# 08_SAMA7G54-DDR3.net
KiCad netlist of a schematic drawn in Altium Designer
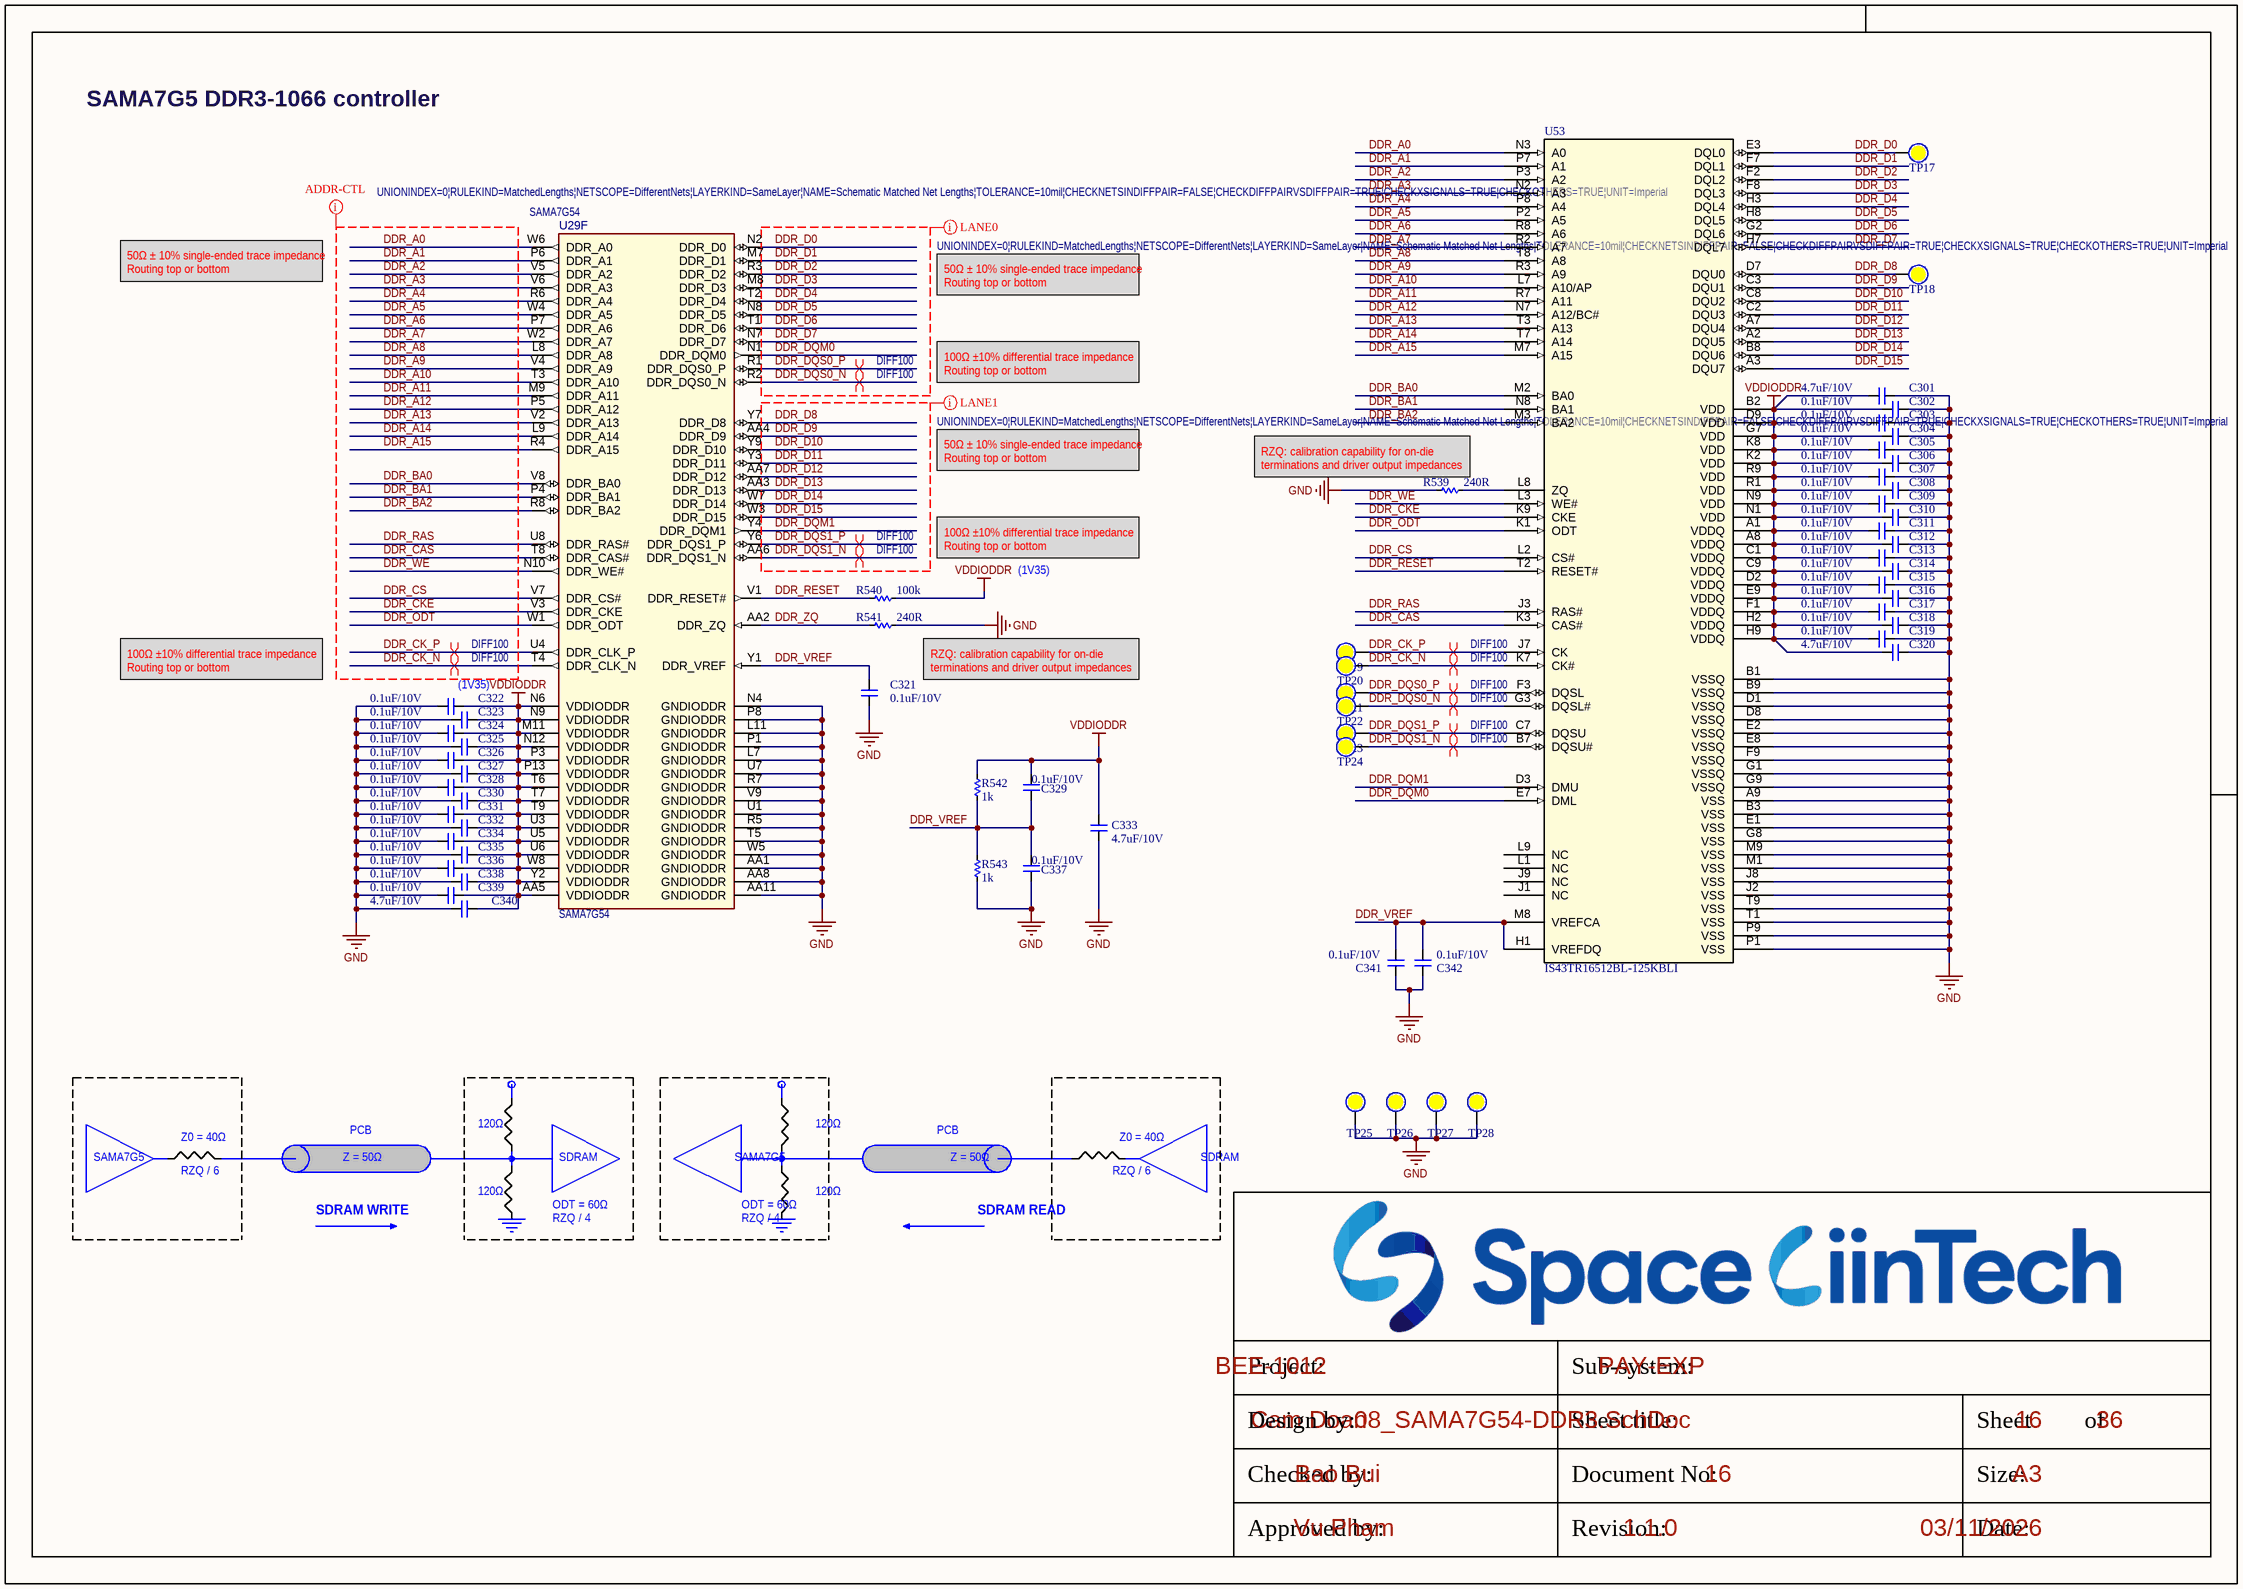
[diagram p0: 08_SAMA7G54-DDR3.SchDoc]

(export (version "E")
  (design (tool "Eeschema 10.0.6"))
  (components
    (comp (ref "C301")
      (value "4.7uF/10V")
      (footprint "CAP_C_1005X50_L")
      (description "CAP")
      (libsource (lib "LABLIB") (part "_CAP_C_2"))
    )
    (comp (ref "C302")
      (value "0.1uF/10V")
      (footprint "CAP_C_0603x30")
      (description "CAP")
      (libsource (lib "LABLIB") (part "_CAP_C_2"))
    )
    (comp (ref "C303")
      (value "0.1uF/10V")
      (footprint "CAP_C_0603x30")
      (description "CAP")
      (libsource (lib "LABLIB") (part "_CAP_C_2"))
    )
    (comp (ref "C304")
      (value "0.1uF/10V")
      (footprint "CAP_C_0603x30")
      (description "CAP")
      (libsource (lib "LABLIB") (part "_CAP_C_2"))
    )
    (comp (ref "C305")
      (value "0.1uF/10V")
      (footprint "CAP_C_0603x30")
      (description "CAP")
      (libsource (lib "LABLIB") (part "_CAP_C_2"))
    )
    (comp (ref "C306")
      (value "0.1uF/10V")
      (footprint "CAP_C_0603x30")
      (description "CAP")
      (libsource (lib "LABLIB") (part "_CAP_C_2"))
    )
    (comp (ref "C307")
      (value "0.1uF/10V")
      (footprint "CAP_C_0603x30")
      (description "CAP")
      (libsource (lib "LABLIB") (part "_CAP_C_2"))
    )
    (comp (ref "C308")
      (value "0.1uF/10V")
      (footprint "CAP_C_0603x30")
      (description "CAP")
      (libsource (lib "LABLIB") (part "_CAP_C_2"))
    )
    (comp (ref "C309")
      (value "0.1uF/10V")
      (footprint "CAP_C_0603x30")
      (description "CAP")
      (libsource (lib "LABLIB") (part "_CAP_C_2"))
    )
    (comp (ref "C310")
      (value "0.1uF/10V")
      (footprint "CAP_C_0603x30")
      (description "CAP")
      (libsource (lib "LABLIB") (part "_CAP_C_2"))
    )
    (comp (ref "C311")
      (value "0.1uF/10V")
      (footprint "CAP_C_0603x30")
      (description "CAP")
      (libsource (lib "LABLIB") (part "_CAP_C_2"))
    )
    (comp (ref "C312")
      (value "0.1uF/10V")
      (footprint "CAP_C_0603x30")
      (description "CAP")
      (libsource (lib "LABLIB") (part "_CAP_C_2"))
    )
    (comp (ref "C313")
      (value "0.1uF/10V")
      (footprint "CAP_C_0603x30")
      (description "CAP")
      (libsource (lib "LABLIB") (part "_CAP_C_2"))
    )
    (comp (ref "C314")
      (value "0.1uF/10V")
      (footprint "CAP_C_0603x30")
      (description "CAP")
      (libsource (lib "LABLIB") (part "_CAP_C_2"))
    )
    (comp (ref "C315")
      (value "0.1uF/10V")
      (footprint "CAP_C_0603x30")
      (description "CAP")
      (libsource (lib "LABLIB") (part "_CAP_C_2"))
    )
    (comp (ref "C316")
      (value "0.1uF/10V")
      (footprint "CAP_C_0603x30")
      (description "CAP")
      (libsource (lib "LABLIB") (part "_CAP_C_2"))
    )
    (comp (ref "C317")
      (value "0.1uF/10V")
      (footprint "CAP_C_0603x30")
      (description "CAP")
      (libsource (lib "LABLIB") (part "_CAP_C_2"))
    )
    (comp (ref "C318")
      (value "0.1uF/10V")
      (footprint "CAP_C_0603x30")
      (description "CAP")
      (libsource (lib "LABLIB") (part "_CAP_C_2"))
    )
    (comp (ref "C319")
      (value "0.1uF/10V")
      (footprint "CAP_C_0603x30")
      (description "CAP")
      (libsource (lib "LABLIB") (part "_CAP_C_2"))
    )
    (comp (ref "C320")
      (value "4.7uF/10V")
      (footprint "CAP_C_1005X50_L")
      (description "CAP")
      (libsource (lib "LABLIB") (part "_CAP_C_2"))
    )
    (comp (ref "C321")
      (value "0.1uF/10V")
      (footprint "CAP_C_0603x30")
      (description "CAP")
      (libsource (lib "LABLIB") (part "_CAP_C_2"))
    )
    (comp (ref "C322")
      (value "0.1uF/10V")
      (footprint "CAP_C_0603x30")
      (description "CAP")
      (libsource (lib "LABLIB") (part "_CAP_C_2"))
    )
    (comp (ref "C323")
      (value "0.1uF/10V")
      (footprint "CAP_C_0603x30")
      (description "CAP")
      (libsource (lib "LABLIB") (part "_CAP_C_2"))
    )
    (comp (ref "C324")
      (value "0.1uF/10V")
      (footprint "CAP_C_0603x30")
      (description "CAP")
      (libsource (lib "LABLIB") (part "_CAP_C_2"))
    )
    (comp (ref "C325")
      (value "0.1uF/10V")
      (footprint "CAP_C_0603x30")
      (description "CAP")
      (libsource (lib "LABLIB") (part "_CAP_C_2"))
    )
    (comp (ref "C326")
      (value "0.1uF/10V")
      (footprint "CAP_C_0603x30")
      (description "CAP")
      (libsource (lib "LABLIB") (part "_CAP_C_2"))
    )
    (comp (ref "C327")
      (value "0.1uF/10V")
      (footprint "CAP_C_0603x30")
      (description "CAP")
      (libsource (lib "LABLIB") (part "_CAP_C_2"))
    )
    (comp (ref "C328")
      (value "0.1uF/10V")
      (footprint "CAP_C_0603x30")
      (description "CAP")
      (libsource (lib "LABLIB") (part "_CAP_C_2"))
    )
    (comp (ref "C329")
      (value "0.1uF/10V")
      (footprint "CAP_C_0603x30")
      (description "CAP")
      (libsource (lib "LABLIB") (part "_CAP_C_2"))
    )
    (comp (ref "C330")
      (value "0.1uF/10V")
      (footprint "CAP_C_0603x30")
      (description "CAP")
      (libsource (lib "LABLIB") (part "_CAP_C_2"))
    )
    (comp (ref "C331")
      (value "0.1uF/10V")
      (footprint "CAP_C_0603x30")
      (description "CAP")
      (libsource (lib "LABLIB") (part "_CAP_C_2"))
    )
    (comp (ref "C332")
      (value "0.1uF/10V")
      (footprint "CAP_C_0603x30")
      (description "CAP")
      (libsource (lib "LABLIB") (part "_CAP_C_2"))
    )
    (comp (ref "C333")
      (value "4.7uF/10V")
      (footprint "CAP_C_1005X50_L")
      (description "CAP")
      (libsource (lib "LABLIB") (part "_CAP_C_2"))
    )
    (comp (ref "C334")
      (value "0.1uF/10V")
      (footprint "CAP_C_0603x30")
      (description "CAP")
      (libsource (lib "LABLIB") (part "_CAP_C_2"))
    )
    (comp (ref "C335")
      (value "0.1uF/10V")
      (footprint "CAP_C_0603x30")
      (description "CAP")
      (libsource (lib "LABLIB") (part "_CAP_C_2"))
    )
    (comp (ref "C336")
      (value "0.1uF/10V")
      (footprint "CAP_C_0603x30")
      (description "CAP")
      (libsource (lib "LABLIB") (part "_CAP_C_2"))
    )
    (comp (ref "C337")
      (value "0.1uF/10V")
      (footprint "CAP_C_0603x30")
      (description "CAP")
      (libsource (lib "LABLIB") (part "_CAP_C_2"))
    )
    (comp (ref "C338")
      (value "0.1uF/10V")
      (footprint "CAP_C_0603x30")
      (description "CAP")
      (libsource (lib "LABLIB") (part "_CAP_C_2"))
    )
    (comp (ref "C339")
      (value "0.1uF/10V")
      (footprint "CAP_C_0603x30")
      (description "CAP")
      (libsource (lib "LABLIB") (part "_CAP_C_2"))
    )
    (comp (ref "C340")
      (value "4.7uF/10V")
      (footprint "CAP_C_1005X50_L")
      (description "CAP")
      (libsource (lib "LABLIB") (part "_CAP_C_2"))
    )
    (comp (ref "C341")
      (value "0.1uF/10V")
      (footprint "CAP_C_0603x30")
      (description "CAP")
      (libsource (lib "LABLIB") (part "_CAP_C_2"))
    )
    (comp (ref "C342")
      (value "0.1uF/10V")
      (footprint "CAP_C_0603x30")
      (description "CAP")
      (libsource (lib "LABLIB") (part "_CAP_C_2"))
    )
    (comp (ref "R539")
      (value "240R")
      (footprint "RES_C_0603X30")
      (description "RES")
      (libsource (lib "LABLIB") (part "_RES_B_2"))
    )
    (comp (ref "R540")
      (value "100k")
      (footprint "RES_C_0603X30")
      (description "RES")
      (libsource (lib "LABLIB") (part "_RES_B_2"))
    )
    (comp (ref "R541")
      (value "240R")
      (footprint "RES_C_0603X30")
      (description "RES")
      (libsource (lib "LABLIB") (part "_RES_B_2"))
    )
    (comp (ref "R542")
      (value "1k")
      (footprint "RES_C_0603X30")
      (description "RES")
      (libsource (lib "LABLIB") (part "_RES_B_2"))
    )
    (comp (ref "R543")
      (value "1k")
      (footprint "RES_C_0603X30")
      (description "RES")
      (libsource (lib "LABLIB") (part "_RES_B_2"))
    )
    (comp (ref "TP17")
      (value "~")
      (footprint "Testpoint_50")
      (description "Test Point")
      (libsource (lib "") (part "Test Point_2"))
    )
    (comp (ref "TP18")
      (value "~")
      (footprint "Testpoint_50")
      (description "Test Point")
      (libsource (lib "") (part "Test Point_2"))
    )
    (comp (ref "TP19")
      (value "~")
      (footprint "Testpoint_50")
      (description "Test Point")
      (libsource (lib "LABLIB") (part "Test Point"))
    )
    (comp (ref "TP20")
      (value "~")
      (footprint "Testpoint_50")
      (description "Test Point")
      (libsource (lib "LABLIB") (part "Test Point"))
    )
    (comp (ref "TP21")
      (value "~")
      (footprint "Testpoint_50")
      (description "Test Point")
      (libsource (lib "LABLIB") (part "Test Point"))
    )
    (comp (ref "TP22")
      (value "~")
      (footprint "Testpoint_50")
      (description "Test Point")
      (libsource (lib "LABLIB") (part "Test Point"))
    )
    (comp (ref "TP23")
      (value "~")
      (footprint "Testpoint_50")
      (description "Test Point")
      (libsource (lib "LABLIB") (part "Test Point"))
    )
    (comp (ref "TP24")
      (value "~")
      (footprint "Testpoint_50")
      (description "Test Point")
      (libsource (lib "LABLIB") (part "Test Point"))
    )
    (comp (ref "TP25")
      (value "~")
      (footprint "Testpoint_50")
      (description "Test Point")
      (libsource (lib "") (part "Test Point_1"))
    )
    (comp (ref "TP26")
      (value "~")
      (footprint "Testpoint_50")
      (description "Test Point")
      (libsource (lib "") (part "Test Point_1"))
    )
    (comp (ref "TP27")
      (value "~")
      (footprint "Testpoint_50")
      (description "Test Point")
      (libsource (lib "") (part "Test Point_1"))
    )
    (comp (ref "TP28")
      (value "~")
      (footprint "Testpoint_50")
      (description "Test Point")
      (libsource (lib "") (part "Test Point_1"))
    )
    (comp (ref "U29")
      (value "SAMA7G54")
      (footprint "TFBGA-343_14x14 - 2.5mm")
      (description "SAMA7G54 MPU 1000MHz Cortex-A7 TFBGA-343")
      (fields (field (name "ALTIUM_VALUE") "SAMA7G54") (field (name "OWNER") "Ciprian Abramov"))
      (libsource (lib "LABLIB") (part "SAMA7G54"))
    )
    (comp (ref "U53")
      (value "IS43TR16512BL-125KBLI")
      (footprint "TWBGA96_ISI")
      (description "DDR3L")
      (fields (field (name "COPYRIGHT") "Copyright (C) 2025 Ultra Librarian. All rights reserved."))
      (libsource (lib "LABLIB") (part "IC_RAM_IS43TR16512BL-125KBLI"))
    )
  )
  (nets
    (net (code "1") (name "/DDR_A0") (class "Default")
      (node (ref "U29") (pin "W6") (pinfunction "DDR_A0_W6") (pintype "output"))
      (node (ref "U53") (pin "N3") (pinfunction "A0_N3") (pintype "input"))
    )
    (net (code "2") (name "/DDR_A1") (class "Default")
      (node (ref "U29") (pin "P6") (pinfunction "DDR_A1_P6") (pintype "output"))
      (node (ref "U53") (pin "P7") (pinfunction "A1_P7") (pintype "input"))
    )
    (net (code "3") (name "/DDR_A2") (class "Default")
      (node (ref "U29") (pin "V5") (pinfunction "DDR_A2_V5") (pintype "output"))
      (node (ref "U53") (pin "P3") (pinfunction "A2_P3") (pintype "input"))
    )
    (net (code "4") (name "/DDR_A3") (class "Default")
      (node (ref "U29") (pin "V6") (pinfunction "DDR_A3_V6") (pintype "output"))
      (node (ref "U53") (pin "N2") (pinfunction "A3_N2") (pintype "input"))
    )
    (net (code "5") (name "/DDR_A4") (class "Default")
      (node (ref "U29") (pin "R6") (pinfunction "DDR_A4_R6") (pintype "output"))
      (node (ref "U53") (pin "P8") (pinfunction "A4_P8") (pintype "input"))
    )
    (net (code "6") (name "/DDR_A5") (class "Default")
      (node (ref "U29") (pin "W4") (pinfunction "DDR_A5_W4") (pintype "output"))
      (node (ref "U53") (pin "P2") (pinfunction "A5_P2") (pintype "input"))
    )
    (net (code "7") (name "/DDR_A6") (class "Default")
      (node (ref "U29") (pin "P7") (pinfunction "DDR_A6_P7") (pintype "output"))
      (node (ref "U53") (pin "R8") (pinfunction "A6_R8") (pintype "input"))
    )
    (net (code "8") (name "/DDR_A7") (class "Default")
      (node (ref "U29") (pin "W2") (pinfunction "DDR_A7_W2") (pintype "output"))
      (node (ref "U53") (pin "R2") (pinfunction "A7_R2") (pintype "input"))
    )
    (net (code "9") (name "/DDR_A8") (class "Default")
      (node (ref "U29") (pin "L8") (pinfunction "DDR_A8_L8") (pintype "output"))
      (node (ref "U53") (pin "T8") (pinfunction "A8_T8") (pintype "input"))
    )
    (net (code "10") (name "/DDR_A9") (class "Default")
      (node (ref "U29") (pin "V4") (pinfunction "DDR_A9_V4") (pintype "output"))
      (node (ref "U53") (pin "R3") (pinfunction "A9_R3") (pintype "input"))
    )
    (net (code "11") (name "/DDR_A10") (class "Default")
      (node (ref "U29") (pin "T3") (pinfunction "DDR_A10_T3") (pintype "output"))
      (node (ref "U53") (pin "L7") (pinfunction "A10/AP_L7") (pintype "input"))
    )
    (net (code "12") (name "/DDR_A11") (class "Default")
      (node (ref "U29") (pin "M9") (pinfunction "DDR_A11_M9") (pintype "output"))
      (node (ref "U53") (pin "R7") (pinfunction "A11_R7") (pintype "input"))
    )
    (net (code "13") (name "/DDR_A12") (class "Default")
      (node (ref "U29") (pin "P5") (pinfunction "DDR_A12_P5") (pintype "output"))
      (node (ref "U53") (pin "N7") (pinfunction "A12/BC#_N7") (pintype "input"))
    )
    (net (code "14") (name "/DDR_A13") (class "Default")
      (node (ref "U29") (pin "V2") (pinfunction "DDR_A13_V2") (pintype "output"))
      (node (ref "U53") (pin "T3") (pinfunction "A13_T3") (pintype "input"))
    )
    (net (code "15") (name "/DDR_A14") (class "Default")
      (node (ref "U29") (pin "L9") (pinfunction "DDR_A14_L9") (pintype "output"))
      (node (ref "U53") (pin "T7") (pinfunction "A14_T7") (pintype "input"))
    )
    (net (code "16") (name "/DDR_A15") (class "Default")
      (node (ref "U29") (pin "R4") (pinfunction "DDR_A15_R4") (pintype "output"))
      (node (ref "U53") (pin "M7") (pinfunction "A15_M7") (pintype "input"))
    )
    (net (code "17") (name "/DDR_BA0") (class "Default")
      (node (ref "U29") (pin "V8") (pinfunction "DDR_BA0_V8") (pintype "bidirectional"))
      (node (ref "U53") (pin "M2") (pinfunction "BA0_M2") (pintype "input"))
    )
    (net (code "18") (name "/DDR_BA1") (class "Default")
      (node (ref "U29") (pin "P4") (pinfunction "DDR_BA1_P4") (pintype "bidirectional"))
      (node (ref "U53") (pin "N8") (pinfunction "BA1_N8") (pintype "input"))
    )
    (net (code "19") (name "/DDR_BA2") (class "Default")
      (node (ref "U29") (pin "R8") (pinfunction "DDR_BA2_R8") (pintype "bidirectional"))
      (node (ref "U53") (pin "M3") (pinfunction "BA2_M3") (pintype "input"))
    )
    (net (code "20") (name "/DDR_CAS") (class "Default")
      (node (ref "U29") (pin "T8") (pinfunction "DDR_CAS#_T8") (pintype "bidirectional"))
      (node (ref "U53") (pin "K3") (pinfunction "CAS#_K3") (pintype "input"))
    )
    (net (code "21") (name "/DDR_CKE") (class "Default")
      (node (ref "U29") (pin "V3") (pinfunction "DDR_CKE_V3") (pintype "output"))
      (node (ref "U53") (pin "K9") (pinfunction "CKE_K9") (pintype "input"))
    )
    (net (code "22") (name "/DDR_CK_N") (class "Default")
      (node (ref "TP20") (pin "1") (pinfunction "1_1") (pintype "passive"))
      (node (ref "U29") (pin "T4") (pinfunction "DDR_CLK_N_T4") (pintype "output"))
      (node (ref "U53") (pin "K7") (pinfunction "CK#_K7") (pintype "input"))
    )
    (net (code "23") (name "/DDR_CK_P") (class "Default")
      (node (ref "TP19") (pin "1") (pinfunction "1_1") (pintype "passive"))
      (node (ref "U29") (pin "U4") (pinfunction "DDR_CLK_P_U4") (pintype "output"))
      (node (ref "U53") (pin "J7") (pinfunction "CK_J7") (pintype "input"))
    )
    (net (code "24") (name "/DDR_CS") (class "Default")
      (node (ref "U29") (pin "V7") (pinfunction "DDR_CS#_V7") (pintype "output"))
      (node (ref "U53") (pin "L2") (pinfunction "CS#_L2") (pintype "input"))
    )
    (net (code "25") (name "/DDR_D0") (class "Default")
      (node (ref "TP17") (pin "1") (pinfunction "1_1") (pintype "passive"))
      (node (ref "U29") (pin "N2") (pinfunction "DDR_D0_N2") (pintype "bidirectional"))
      (node (ref "U53") (pin "E3") (pinfunction "DQL0_E3") (pintype "bidirectional"))
    )
    (net (code "26") (name "/DDR_D1") (class "Default")
      (node (ref "U29") (pin "M7") (pinfunction "DDR_D1_M7") (pintype "bidirectional"))
      (node (ref "U53") (pin "F7") (pinfunction "DQL1_F7") (pintype "bidirectional"))
    )
    (net (code "27") (name "/DDR_D2") (class "Default")
      (node (ref "U29") (pin "R3") (pinfunction "DDR_D2_R3") (pintype "bidirectional"))
      (node (ref "U53") (pin "F2") (pinfunction "DQL2_F2") (pintype "bidirectional"))
    )
    (net (code "28") (name "/DDR_D3") (class "Default")
      (node (ref "U29") (pin "M8") (pinfunction "DDR_D3_M8") (pintype "bidirectional"))
      (node (ref "U53") (pin "F8") (pinfunction "DQL3_F8") (pintype "bidirectional"))
    )
    (net (code "29") (name "/DDR_D4") (class "Default")
      (node (ref "U29") (pin "T2") (pinfunction "DDR_D4_T2") (pintype "bidirectional"))
      (node (ref "U53") (pin "H3") (pinfunction "DQL4_H3") (pintype "bidirectional"))
    )
    (net (code "30") (name "/DDR_D5") (class "Default")
      (node (ref "U29") (pin "N8") (pinfunction "DDR_D5_N8") (pintype "bidirectional"))
      (node (ref "U53") (pin "H8") (pinfunction "DQL5_H8") (pintype "bidirectional"))
    )
    (net (code "31") (name "/DDR_D6") (class "Default")
      (node (ref "U29") (pin "T1") (pinfunction "DDR_D6_T1") (pintype "bidirectional"))
      (node (ref "U53") (pin "G2") (pinfunction "DQL6_G2") (pintype "bidirectional"))
    )
    (net (code "32") (name "/DDR_D7") (class "Default")
      (node (ref "U29") (pin "N7") (pinfunction "DDR_D7_N7") (pintype "bidirectional"))
      (node (ref "U53") (pin "H7") (pinfunction "DQL7_H7") (pintype "bidirectional"))
    )
    (net (code "33") (name "/DDR_D8") (class "Default")
      (node (ref "TP18") (pin "1") (pinfunction "1_1") (pintype "passive"))
      (node (ref "U29") (pin "Y7") (pinfunction "DDR_D8_Y7") (pintype "bidirectional"))
      (node (ref "U53") (pin "D7") (pinfunction "DQU0_D7") (pintype "bidirectional"))
    )
    (net (code "34") (name "/DDR_D9") (class "Default")
      (node (ref "U29") (pin "AA4") (pinfunction "DDR_D9_AA4") (pintype "bidirectional"))
      (node (ref "U53") (pin "C3") (pinfunction "DQU1_C3") (pintype "bidirectional"))
    )
    (net (code "35") (name "/DDR_D10") (class "Default")
      (node (ref "U29") (pin "Y9") (pinfunction "DDR_D10_Y9") (pintype "bidirectional"))
      (node (ref "U53") (pin "C8") (pinfunction "DQU2_C8") (pintype "bidirectional"))
    )
    (net (code "36") (name "/DDR_D11") (class "Default")
      (node (ref "U29") (pin "Y3") (pinfunction "DDR_D11_Y3") (pintype "bidirectional"))
      (node (ref "U53") (pin "C2") (pinfunction "DQU3_C2") (pintype "bidirectional"))
    )
    (net (code "37") (name "/DDR_D12") (class "Default")
      (node (ref "U29") (pin "AA7") (pinfunction "DDR_D12_AA7") (pintype "bidirectional"))
      (node (ref "U53") (pin "A7") (pinfunction "DQU4_A7") (pintype "bidirectional"))
    )
    (net (code "38") (name "/DDR_D13") (class "Default")
      (node (ref "U29") (pin "AA3") (pinfunction "DDR_D13_AA3") (pintype "bidirectional"))
      (node (ref "U53") (pin "A2") (pinfunction "DQU5_A2") (pintype "bidirectional"))
    )
    (net (code "39") (name "/DDR_D14") (class "Default")
      (node (ref "U29") (pin "W7") (pinfunction "DDR_D14_W7") (pintype "bidirectional"))
      (node (ref "U53") (pin "B8") (pinfunction "DQU6_B8") (pintype "bidirectional"))
    )
    (net (code "40") (name "/DDR_D15") (class "Default")
      (node (ref "U29") (pin "W3") (pinfunction "DDR_D15_W3") (pintype "bidirectional"))
      (node (ref "U53") (pin "A3") (pinfunction "DQU7_A3") (pintype "bidirectional"))
    )
    (net (code "41") (name "/DDR_DQM0") (class "Default")
      (node (ref "U29") (pin "N1") (pinfunction "DDR_DQM0_N1") (pintype "output"))
      (node (ref "U53") (pin "E7") (pinfunction "DML_E7") (pintype "input"))
    )
    (net (code "42") (name "/DDR_DQM1") (class "Default")
      (node (ref "U29") (pin "Y4") (pinfunction "DDR_DQM1_Y4") (pintype "output"))
      (node (ref "U53") (pin "D3") (pinfunction "DMU_D3") (pintype "input"))
    )
    (net (code "43") (name "/DDR_DQS0_N") (class "Default")
      (node (ref "TP22") (pin "1") (pinfunction "1_1") (pintype "passive"))
      (node (ref "U29") (pin "R2") (pinfunction "DDR_DQS0_N_R2") (pintype "bidirectional"))
      (node (ref "U53") (pin "G3") (pinfunction "DQSL#_G3") (pintype "bidirectional"))
    )
    (net (code "44") (name "/DDR_DQS0_P") (class "Default")
      (node (ref "TP21") (pin "1") (pinfunction "1_1") (pintype "passive"))
      (node (ref "U29") (pin "R1") (pinfunction "DDR_DQS0_P_R1") (pintype "bidirectional"))
      (node (ref "U53") (pin "F3") (pinfunction "DQSL_F3") (pintype "bidirectional"))
    )
    (net (code "45") (name "/DDR_DQS1_N") (class "Default")
      (node (ref "TP24") (pin "1") (pinfunction "1_1") (pintype "passive"))
      (node (ref "U29") (pin "AA6") (pinfunction "DDR_DQS1_N_AA6") (pintype "bidirectional"))
      (node (ref "U53") (pin "B7") (pinfunction "DQSU#_B7") (pintype "bidirectional"))
    )
    (net (code "46") (name "/DDR_DQS1_P") (class "Default")
      (node (ref "TP23") (pin "1") (pinfunction "1_1") (pintype "passive"))
      (node (ref "U29") (pin "Y6") (pinfunction "DDR_DQS1_P_Y6") (pintype "bidirectional"))
      (node (ref "U53") (pin "C7") (pinfunction "DQSU_C7") (pintype "bidirectional"))
    )
    (net (code "47") (name "/DDR_ODT") (class "Default")
      (node (ref "U29") (pin "W1") (pinfunction "DDR_ODT_W1") (pintype "output"))
      (node (ref "U53") (pin "K1") (pinfunction "ODT_K1") (pintype "input"))
    )
    (net (code "48") (name "/DDR_RAS") (class "Default")
      (node (ref "U29") (pin "U8") (pinfunction "DDR_RAS#_U8") (pintype "bidirectional"))
      (node (ref "U53") (pin "J3") (pinfunction "RAS#_J3") (pintype "input"))
    )
    (net (code "49") (name "/DDR_RESET") (class "Default")
      (node (ref "R540") (pin "2") (pinfunction "2_2") (pintype "passive"))
      (node (ref "U29") (pin "V1") (pinfunction "DDR_RESET#_V1") (pintype "output"))
      (node (ref "U53") (pin "T2") (pinfunction "RESET#_T2") (pintype "input"))
    )
    (net (code "50") (name "/DDR_VREF") (class "Default")
      (node (ref "C321") (pin "1") (pinfunction "1_1") (pintype "passive"))
      (node (ref "C329") (pin "2") (pinfunction "2_2") (pintype "passive"))
      (node (ref "C337") (pin "1") (pinfunction "1_1") (pintype "passive"))
      (node (ref "C341") (pin "1") (pinfunction "1_1") (pintype "passive"))
      (node (ref "C342") (pin "1") (pinfunction "1_1") (pintype "passive"))
      (node (ref "R542") (pin "2") (pinfunction "2_2") (pintype "passive"))
      (node (ref "R543") (pin "1") (pinfunction "1_1") (pintype "passive"))
      (node (ref "U29") (pin "Y1") (pinfunction "DDR_VREF_Y1") (pintype "input"))
      (node (ref "U53") (pin "H1") (pinfunction "VREFDQ_H1") (pintype "power_in"))
      (node (ref "U53") (pin "M8") (pinfunction "VREFCA_M8") (pintype "power_in"))
    )
    (net (code "51") (name "/DDR_WE") (class "Default")
      (node (ref "U29") (pin "N10") (pinfunction "DDR_WE#_N10") (pintype "output"))
      (node (ref "U53") (pin "L3") (pinfunction "WE#_L3") (pintype "input"))
    )
    (net (code "52") (name "/DDR_ZQ") (class "Default")
      (node (ref "R541") (pin "2") (pinfunction "2_2") (pintype "passive"))
      (node (ref "U29") (pin "AA2") (pinfunction "DDR_ZQ_AA2") (pintype "input"))
    )
    (net (code "53") (name "GND") (class "Default")
      (node (ref "C301") (pin "1") (pinfunction "1_1") (pintype "passive"))
      (node (ref "C302") (pin "1") (pinfunction "1_1") (pintype "passive"))
      (node (ref "C303") (pin "1") (pinfunction "1_1") (pintype "passive"))
      (node (ref "C304") (pin "1") (pinfunction "1_1") (pintype "passive"))
      (node (ref "C305") (pin "1") (pinfunction "1_1") (pintype "passive"))
      (node (ref "C306") (pin "1") (pinfunction "1_1") (pintype "passive"))
      (node (ref "C307") (pin "1") (pinfunction "1_1") (pintype "passive"))
      (node (ref "C308") (pin "1") (pinfunction "1_1") (pintype "passive"))
      (node (ref "C309") (pin "1") (pinfunction "1_1") (pintype "passive"))
      (node (ref "C310") (pin "1") (pinfunction "1_1") (pintype "passive"))
      (node (ref "C311") (pin "1") (pinfunction "1_1") (pintype "passive"))
      (node (ref "C312") (pin "1") (pinfunction "1_1") (pintype "passive"))
      (node (ref "C313") (pin "1") (pinfunction "1_1") (pintype "passive"))
      (node (ref "C314") (pin "1") (pinfunction "1_1") (pintype "passive"))
      (node (ref "C315") (pin "1") (pinfunction "1_1") (pintype "passive"))
      (node (ref "C316") (pin "1") (pinfunction "1_1") (pintype "passive"))
      (node (ref "C317") (pin "1") (pinfunction "1_1") (pintype "passive"))
      (node (ref "C318") (pin "1") (pinfunction "1_1") (pintype "passive"))
      (node (ref "C319") (pin "1") (pinfunction "1_1") (pintype "passive"))
      (node (ref "C320") (pin "1") (pinfunction "1_1") (pintype "passive"))
      (node (ref "C321") (pin "2") (pinfunction "2_2") (pintype "passive"))
      (node (ref "C322") (pin "2") (pinfunction "2_2") (pintype "passive"))
      (node (ref "C323") (pin "2") (pinfunction "2_2") (pintype "passive"))
      (node (ref "C324") (pin "2") (pinfunction "2_2") (pintype "passive"))
      (node (ref "C325") (pin "2") (pinfunction "2_2") (pintype "passive"))
      (node (ref "C326") (pin "2") (pinfunction "2_2") (pintype "passive"))
      (node (ref "C327") (pin "2") (pinfunction "2_2") (pintype "passive"))
      (node (ref "C328") (pin "2") (pinfunction "2_2") (pintype "passive"))
      (node (ref "C330") (pin "2") (pinfunction "2_2") (pintype "passive"))
      (node (ref "C331") (pin "2") (pinfunction "2_2") (pintype "passive"))
      (node (ref "C332") (pin "2") (pinfunction "2_2") (pintype "passive"))
      (node (ref "C333") (pin "2") (pinfunction "2_2") (pintype "passive"))
      (node (ref "C334") (pin "2") (pinfunction "2_2") (pintype "passive"))
      (node (ref "C335") (pin "2") (pinfunction "2_2") (pintype "passive"))
      (node (ref "C336") (pin "2") (pinfunction "2_2") (pintype "passive"))
      (node (ref "C337") (pin "2") (pinfunction "2_2") (pintype "passive"))
      (node (ref "C338") (pin "2") (pinfunction "2_2") (pintype "passive"))
      (node (ref "C339") (pin "2") (pinfunction "2_2") (pintype "passive"))
      (node (ref "C340") (pin "2") (pinfunction "2_2") (pintype "passive"))
      (node (ref "C341") (pin "2") (pinfunction "2_2") (pintype "passive"))
      (node (ref "C342") (pin "2") (pinfunction "2_2") (pintype "passive"))
      (node (ref "R539") (pin "2") (pinfunction "2_2") (pintype "passive"))
      (node (ref "R541") (pin "1") (pinfunction "1_1") (pintype "passive"))
      (node (ref "R543") (pin "2") (pinfunction "2_2") (pintype "passive"))
      (node (ref "TP25") (pin "1") (pinfunction "1_1") (pintype "passive"))
      (node (ref "TP26") (pin "1") (pinfunction "1_1") (pintype "passive"))
      (node (ref "TP27") (pin "1") (pinfunction "1_1") (pintype "passive"))
      (node (ref "TP28") (pin "1") (pinfunction "1_1") (pintype "passive"))
      (node (ref "U29") (pin "AA1") (pinfunction "GNDIODDR_AA1") (pintype "power_in"))
      (node (ref "U29") (pin "AA11") (pinfunction "GNDIODDR_AA11") (pintype "power_in"))
      (node (ref "U29") (pin "AA8") (pinfunction "GNDIODDR_AA8") (pintype "power_in"))
      (node (ref "U29") (pin "L11") (pinfunction "GNDIODDR_L11") (pintype "power_in"))
      (node (ref "U29") (pin "L7") (pinfunction "GNDIODDR_L7") (pintype "power_in"))
      (node (ref "U29") (pin "N4") (pinfunction "GNDIODDR_N4") (pintype "power_in"))
      (node (ref "U29") (pin "P1") (pinfunction "GNDIODDR_P1") (pintype "power_in"))
      (node (ref "U29") (pin "P8") (pinfunction "GNDIODDR_P8") (pintype "power_in"))
      (node (ref "U29") (pin "R5") (pinfunction "GNDIODDR_R5") (pintype "power_in"))
      (node (ref "U29") (pin "R7") (pinfunction "GNDIODDR_R7") (pintype "power_in"))
      (node (ref "U29") (pin "T5") (pinfunction "GNDIODDR_T5") (pintype "power_in"))
      (node (ref "U29") (pin "U1") (pinfunction "GNDIODDR_U1") (pintype "power_in"))
      (node (ref "U29") (pin "U7") (pinfunction "GNDIODDR_U7") (pintype "power_in"))
      (node (ref "U29") (pin "V9") (pinfunction "GNDIODDR_V9") (pintype "power_in"))
      (node (ref "U29") (pin "W5") (pinfunction "GNDIODDR_W5") (pintype "power_in"))
      (node (ref "U53") (pin "A9") (pinfunction "VSS_A9") (pintype "power_in"))
      (node (ref "U53") (pin "B1") (pinfunction "VSSQ_B1") (pintype "power_in"))
      (node (ref "U53") (pin "B3") (pinfunction "VSS_B3") (pintype "power_in"))
      (node (ref "U53") (pin "B9") (pinfunction "VSSQ_B9") (pintype "power_in"))
      (node (ref "U53") (pin "D1") (pinfunction "VSSQ_D1") (pintype "power_in"))
      (node (ref "U53") (pin "D8") (pinfunction "VSSQ_D8") (pintype "power_in"))
      (node (ref "U53") (pin "E1") (pinfunction "VSS_E1") (pintype "power_in"))
      (node (ref "U53") (pin "E2") (pinfunction "VSSQ_E2") (pintype "power_in"))
      (node (ref "U53") (pin "E8") (pinfunction "VSSQ_E8") (pintype "power_in"))
      (node (ref "U53") (pin "F9") (pinfunction "VSSQ_F9") (pintype "power_in"))
      (node (ref "U53") (pin "G1") (pinfunction "VSSQ_G1") (pintype "power_in"))
      (node (ref "U53") (pin "G8") (pinfunction "VSS_G8") (pintype "power_in"))
      (node (ref "U53") (pin "G9") (pinfunction "VSSQ_G9") (pintype "power_in"))
      (node (ref "U53") (pin "J2") (pinfunction "VSS_J2") (pintype "power_in"))
      (node (ref "U53") (pin "J8") (pinfunction "VSS_J8") (pintype "power_in"))
      (node (ref "U53") (pin "M1") (pinfunction "VSS_M1") (pintype "power_in"))
      (node (ref "U53") (pin "M9") (pinfunction "VSS_M9") (pintype "power_in"))
      (node (ref "U53") (pin "P1") (pinfunction "VSS_P1") (pintype "power_in"))
      (node (ref "U53") (pin "P9") (pinfunction "VSS_P9") (pintype "power_in"))
      (node (ref "U53") (pin "T1") (pinfunction "VSS_T1") (pintype "power_in"))
      (node (ref "U53") (pin "T9") (pinfunction "VSS_T9") (pintype "power_in"))
    )
    (net (code "54") (name "Net-(U53-ZQ)") (class "Default")
      (node (ref "R539") (pin "1") (pinfunction "1_1") (pintype "passive"))
      (node (ref "U53") (pin "L8") (pinfunction "ZQ_L8") (pintype "power_in"))
    )
    (net (code "55") (name "VDDIODDR") (class "Default")
      (node (ref "C301") (pin "2") (pinfunction "2_2") (pintype "passive"))
      (node (ref "C302") (pin "2") (pinfunction "2_2") (pintype "passive"))
      (node (ref "C303") (pin "2") (pinfunction "2_2") (pintype "passive"))
      (node (ref "C304") (pin "2") (pinfunction "2_2") (pintype "passive"))
      (node (ref "C305") (pin "2") (pinfunction "2_2") (pintype "passive"))
      (node (ref "C306") (pin "2") (pinfunction "2_2") (pintype "passive"))
      (node (ref "C307") (pin "2") (pinfunction "2_2") (pintype "passive"))
      (node (ref "C308") (pin "2") (pinfunction "2_2") (pintype "passive"))
      (node (ref "C309") (pin "2") (pinfunction "2_2") (pintype "passive"))
      (node (ref "C310") (pin "2") (pinfunction "2_2") (pintype "passive"))
      (node (ref "C311") (pin "2") (pinfunction "2_2") (pintype "passive"))
      (node (ref "C312") (pin "2") (pinfunction "2_2") (pintype "passive"))
      (node (ref "C313") (pin "2") (pinfunction "2_2") (pintype "passive"))
      (node (ref "C314") (pin "2") (pinfunction "2_2") (pintype "passive"))
      (node (ref "C315") (pin "2") (pinfunction "2_2") (pintype "passive"))
      (node (ref "C316") (pin "2") (pinfunction "2_2") (pintype "passive"))
      (node (ref "C317") (pin "2") (pinfunction "2_2") (pintype "passive"))
      (node (ref "C318") (pin "2") (pinfunction "2_2") (pintype "passive"))
      (node (ref "C319") (pin "2") (pinfunction "2_2") (pintype "passive"))
      (node (ref "C320") (pin "2") (pinfunction "2_2") (pintype "passive"))
      (node (ref "C322") (pin "1") (pinfunction "1_1") (pintype "passive"))
      (node (ref "C323") (pin "1") (pinfunction "1_1") (pintype "passive"))
      (node (ref "C324") (pin "1") (pinfunction "1_1") (pintype "passive"))
      (node (ref "C325") (pin "1") (pinfunction "1_1") (pintype "passive"))
      (node (ref "C326") (pin "1") (pinfunction "1_1") (pintype "passive"))
      (node (ref "C327") (pin "1") (pinfunction "1_1") (pintype "passive"))
      (node (ref "C328") (pin "1") (pinfunction "1_1") (pintype "passive"))
      (node (ref "C329") (pin "1") (pinfunction "1_1") (pintype "passive"))
      (node (ref "C330") (pin "1") (pinfunction "1_1") (pintype "passive"))
      (node (ref "C331") (pin "1") (pinfunction "1_1") (pintype "passive"))
      (node (ref "C332") (pin "1") (pinfunction "1_1") (pintype "passive"))
      (node (ref "C333") (pin "1") (pinfunction "1_1") (pintype "passive"))
      (node (ref "C334") (pin "1") (pinfunction "1_1") (pintype "passive"))
      (node (ref "C335") (pin "1") (pinfunction "1_1") (pintype "passive"))
      (node (ref "C336") (pin "1") (pinfunction "1_1") (pintype "passive"))
      (node (ref "C338") (pin "1") (pinfunction "1_1") (pintype "passive"))
      (node (ref "C339") (pin "1") (pinfunction "1_1") (pintype "passive"))
      (node (ref "C340") (pin "1") (pinfunction "1_1") (pintype "passive"))
      (node (ref "R540") (pin "1") (pinfunction "1_1") (pintype "passive"))
      (node (ref "R542") (pin "1") (pinfunction "1_1") (pintype "passive"))
      (node (ref "U29") (pin "AA5") (pinfunction "VDDIODDR_AA5") (pintype "power_in"))
      (node (ref "U29") (pin "M11") (pinfunction "VDDIODDR_M11") (pintype "power_in"))
      (node (ref "U29") (pin "N12") (pinfunction "VDDIODDR_N12") (pintype "power_in"))
      (node (ref "U29") (pin "N6") (pinfunction "VDDIODDR_N6") (pintype "power_in"))
      (node (ref "U29") (pin "N9") (pinfunction "VDDIODDR_N9") (pintype "power_in"))
      (node (ref "U29") (pin "P13") (pinfunction "VDDIODDR_P13") (pintype "power_in"))
      (node (ref "U29") (pin "P3") (pinfunction "VDDIODDR_P3") (pintype "power_in"))
      (node (ref "U29") (pin "T6") (pinfunction "VDDIODDR_T6") (pintype "power_in"))
      (node (ref "U29") (pin "T7") (pinfunction "VDDIODDR_T7") (pintype "power_in"))
      (node (ref "U29") (pin "T9") (pinfunction "VDDIODDR_T9") (pintype "power_in"))
      (node (ref "U29") (pin "U3") (pinfunction "VDDIODDR_U3") (pintype "power_in"))
      (node (ref "U29") (pin "U5") (pinfunction "VDDIODDR_U5") (pintype "power_in"))
      (node (ref "U29") (pin "U6") (pinfunction "VDDIODDR_U6") (pintype "power_in"))
      (node (ref "U29") (pin "W8") (pinfunction "VDDIODDR_W8") (pintype "power_in"))
      (node (ref "U29") (pin "Y2") (pinfunction "VDDIODDR_Y2") (pintype "power_in"))
      (node (ref "U53") (pin "A1") (pinfunction "VDDQ_A1") (pintype "power_in"))
      (node (ref "U53") (pin "A8") (pinfunction "VDDQ_A8") (pintype "power_in"))
      (node (ref "U53") (pin "B2") (pinfunction "VDD_B2") (pintype "power_in"))
      (node (ref "U53") (pin "C1") (pinfunction "VDDQ_C1") (pintype "power_in"))
      (node (ref "U53") (pin "C9") (pinfunction "VDDQ_C9") (pintype "power_in"))
      (node (ref "U53") (pin "D2") (pinfunction "VDDQ_D2") (pintype "power_in"))
      (node (ref "U53") (pin "D9") (pinfunction "VDD_D9") (pintype "power_in"))
      (node (ref "U53") (pin "E9") (pinfunction "VDDQ_E9") (pintype "power_in"))
      (node (ref "U53") (pin "F1") (pinfunction "VDDQ_F1") (pintype "power_in"))
      (node (ref "U53") (pin "G7") (pinfunction "VDD_G7") (pintype "power_in"))
      (node (ref "U53") (pin "H2") (pinfunction "VDDQ_H2") (pintype "power_in"))
      (node (ref "U53") (pin "H9") (pinfunction "VDDQ_H9") (pintype "power_in"))
      (node (ref "U53") (pin "K2") (pinfunction "VDD_K2") (pintype "power_in"))
      (node (ref "U53") (pin "K8") (pinfunction "VDD_K8") (pintype "power_in"))
      (node (ref "U53") (pin "N1") (pinfunction "VDD_N1") (pintype "power_in"))
      (node (ref "U53") (pin "N9") (pinfunction "VDD_N9") (pintype "power_in"))
      (node (ref "U53") (pin "R1") (pinfunction "VDD_R1") (pintype "power_in"))
      (node (ref "U53") (pin "R9") (pinfunction "VDD_R9") (pintype "power_in"))
    )
    (net (code "56") (name "unconnected-(U53-NC-PadJ1)") (class "Default")
      (node (ref "U53") (pin "J1") (pinfunction "NC_J1") (pintype "passive"))
    )
    (net (code "57") (name "unconnected-(U53-NC-PadJ9)") (class "Default")
      (node (ref "U53") (pin "J9") (pinfunction "NC_J9") (pintype "passive"))
    )
    (net (code "58") (name "unconnected-(U53-NC-PadL1)") (class "Default")
      (node (ref "U53") (pin "L1") (pinfunction "NC_L1") (pintype "passive"))
    )
    (net (code "59") (name "unconnected-(U53-NC-PadL9)") (class "Default")
      (node (ref "U53") (pin "L9") (pinfunction "NC_L9") (pintype "passive"))
    )
  )
)
